# Synth_2.net
KiCad netlist of a schematic drawn in EAGLE
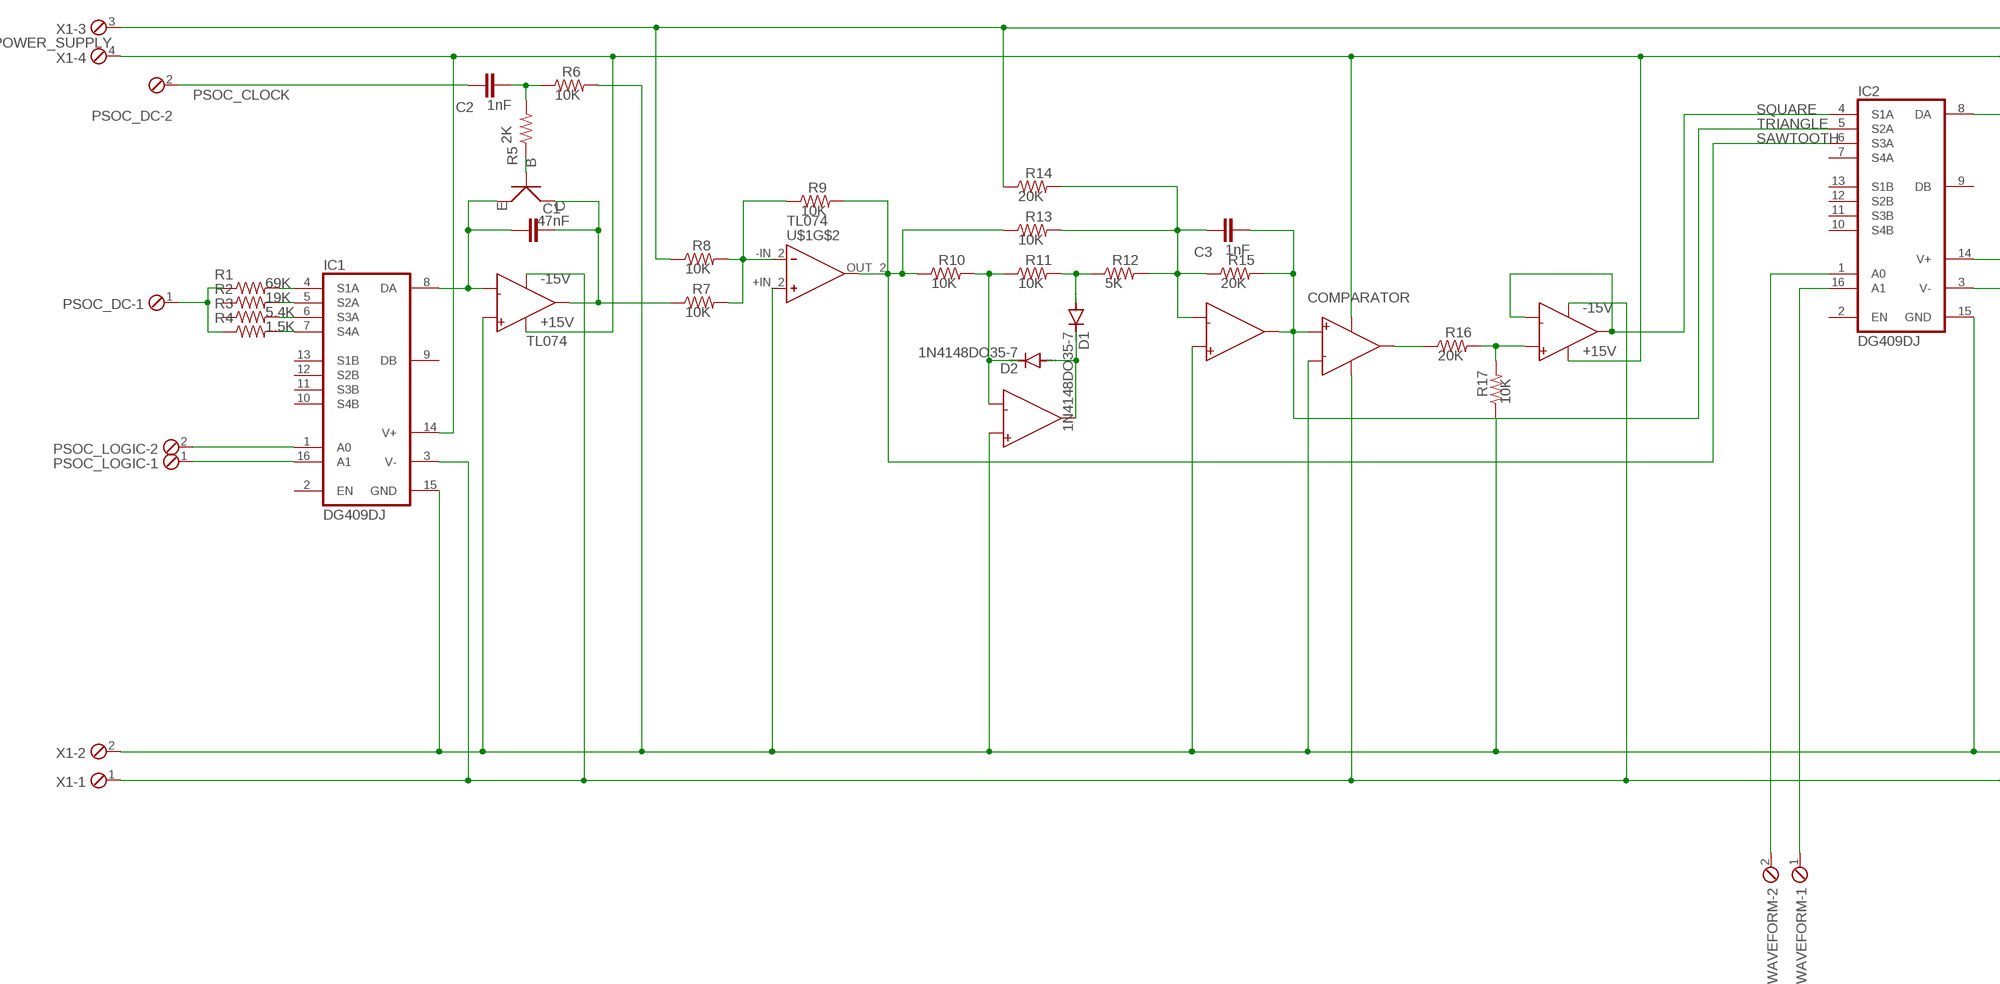
[diagram p0: schematic, sheet 1, part 1 of 2]
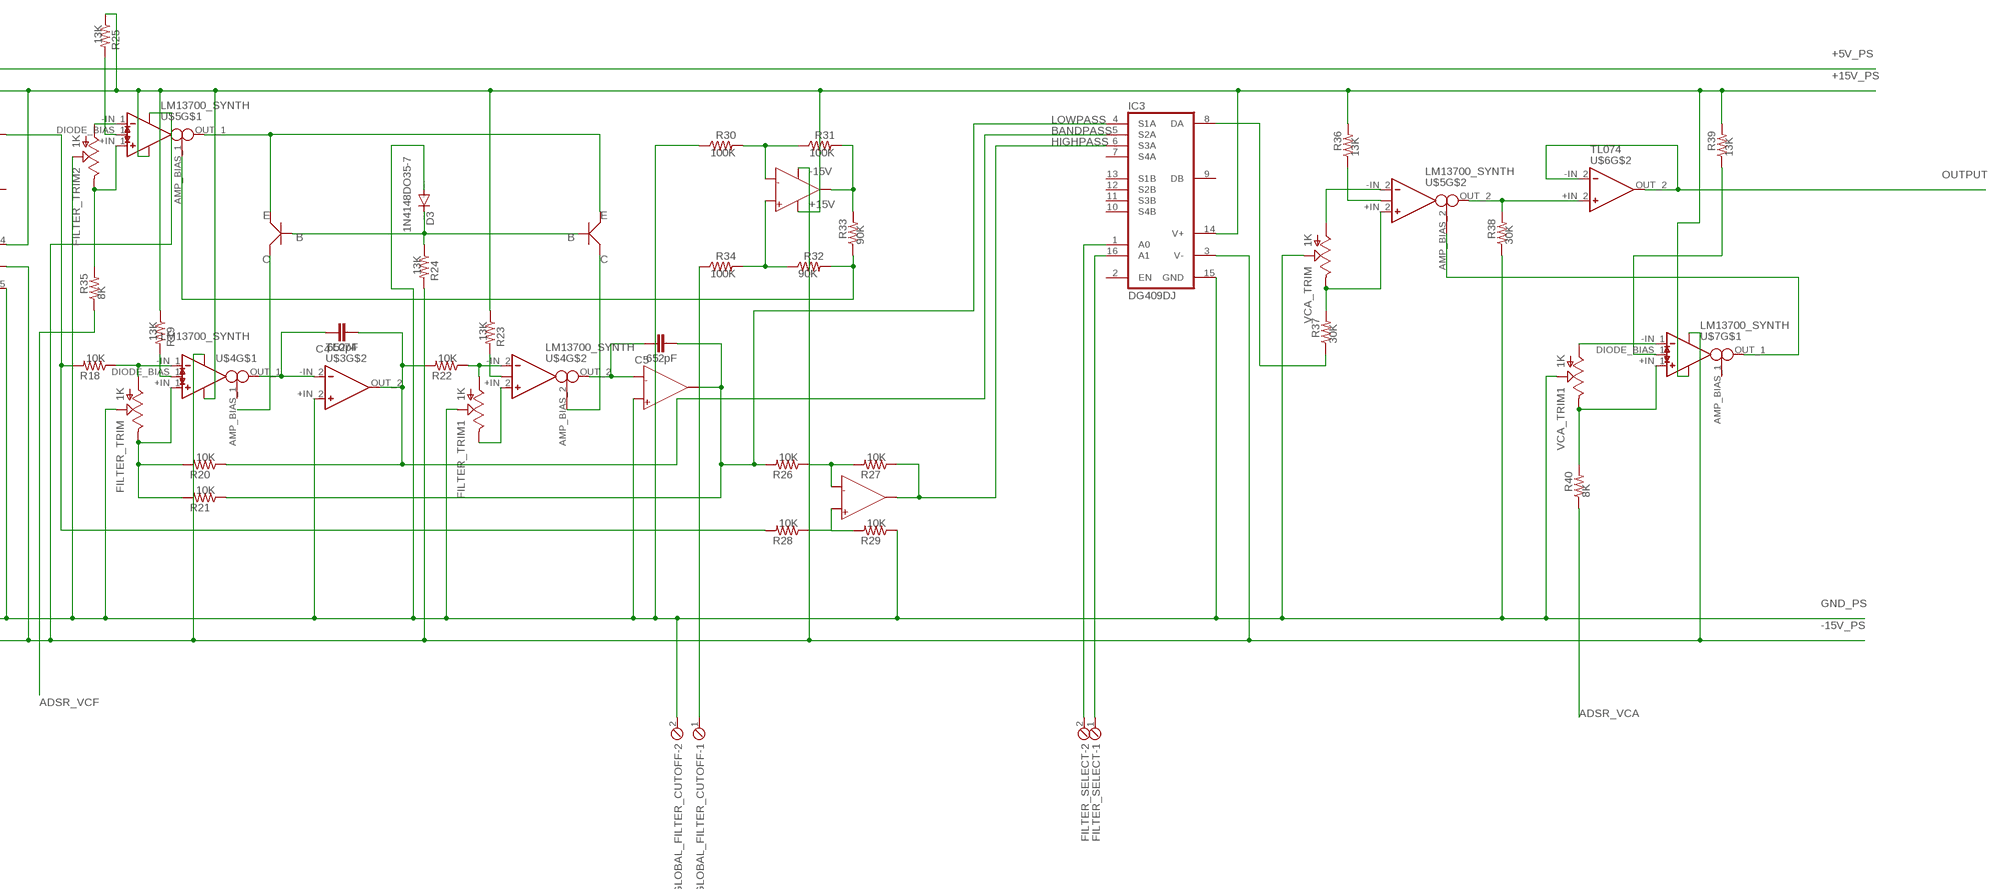
[diagram p1: schematic, sheet 1, part 2 of 2]

(export (version "E")
  (design (tool "Eeschema 10.0.6"))
  (components
    (comp (ref "C1")
      (value "C-EU025-024X044")
      (footprint "eagle-import:C025-024X044")
      (fields (field (name "SPICEPREFIX") "C") (field (name "SPICEPREFIX_1") "47nF"))
      (libsource (lib "eagle-import") (part "C-EU025-024X044"))
    )
    (comp (ref "C2")
      (value "C-EU025-024X044")
      (footprint "eagle-import:C025-024X044")
      (fields (field (name "SPICEPREFIX") "C") (field (name "SPICEPREFIX_1") "1nF"))
      (libsource (lib "eagle-import") (part "C-EU025-024X044"))
    )
    (comp (ref "C3")
      (value "C-EU025-024X044")
      (footprint "eagle-import:C025-024X044")
      (fields (field (name "SPICEPREFIX") "C") (field (name "SPICEPREFIX_1") "1nF"))
      (libsource (lib "eagle-import") (part "C-EU025-024X044"))
    )
    (comp (ref "C4")
      (value "C-EU025-024X044")
      (footprint "eagle-import:C025-024X044")
      (fields (field (name "SPICEPREFIX") "C") (field (name "SPICEPREFIX_1") "652pF"))
      (libsource (lib "eagle-import") (part "C-EU025-024X044"))
    )
    (comp (ref "C5")
      (value "C-EU025-024X044")
      (footprint "eagle-import:C025-024X044")
      (fields (field (name "SPICEPREFIX") "C") (field (name "SPICEPREFIX_1") "652pF"))
      (libsource (lib "eagle-import") (part "C-EU025-024X044"))
    )
    (comp (ref "D1")
      (value "1N4148DO35-7")
      (footprint "eagle-import:DO35-7")
      (libsource (lib "eagle-import") (part "1N4148DO35-7"))
    )
    (comp (ref "D2")
      (value "1N4148DO35-7")
      (footprint "eagle-import:DO35-7")
      (libsource (lib "eagle-import") (part "1N4148DO35-7"))
    )
    (comp (ref "D3")
      (value "1N4148DO35-7")
      (footprint "eagle-import:DO35-7")
      (libsource (lib "eagle-import") (part "1N4148DO35-7"))
    )
    (comp (ref "FILTER_SELECT")
      (value "MPT2")
      (footprint "eagle-import:2POL254")
      (libsource (lib "eagle-import") (part "MPT2"))
    )
    (comp (ref "FILTER_TRIM")
      (value "TRIM_US-CT6")
      (footprint "eagle-import:CT6")
      (fields (field (name "POPULARITY") "2") (field (name "POPULARITY_1") "1K"))
      (libsource (lib "eagle-import") (part "TRIM_US-CT6"))
    )
    (comp (ref "FILTER_TRIM1")
      (value "TRIM_US-CT6")
      (footprint "eagle-import:CT6")
      (fields (field (name "POPULARITY") "2") (field (name "POPULARITY_1") "1K"))
      (libsource (lib "eagle-import") (part "TRIM_US-CT6"))
    )
    (comp (ref "FILTER_TRIM2")
      (value "TRIM_US-CT6")
      (footprint "eagle-import:CT6")
      (fields (field (name "POPULARITY") "2") (field (name "POPULARITY_1") "1K"))
      (libsource (lib "eagle-import") (part "TRIM_US-CT6"))
    )
    (comp (ref "GLOBAL_FILTER_CUTOFF")
      (value "MPT2")
      (footprint "eagle-import:2POL254")
      (libsource (lib "eagle-import") (part "MPT2"))
    )
    (comp (ref "IC1")
      (value "DG409DJ")
      (footprint "eagle-import:DIL16")
      (fields (field (name "MF") "INTERSIL"))
      (libsource (lib "eagle-import") (part "DG409DJ"))
    )
    (comp (ref "IC2")
      (value "DG409DJ")
      (footprint "eagle-import:DIL16")
      (fields (field (name "MF") "INTERSIL"))
      (libsource (lib "eagle-import") (part "DG409DJ"))
    )
    (comp (ref "IC3")
      (value "DG409DJ")
      (footprint "eagle-import:DIL16")
      (fields (field (name "MF") "INTERSIL"))
      (libsource (lib "eagle-import") (part "DG409DJ"))
    )
    (comp (ref "LM293")
      (value "LM293")
      (footprint "eagle-import:LM293")
      (libsource (lib "eagle-import") (part "LM293"))
    )
    (comp (ref "PSOC_DC")
      (value "MPT2")
      (footprint "eagle-import:2POL254")
      (libsource (lib "eagle-import") (part "MPT2"))
    )
    (comp (ref "PSOC_LOGIC")
      (value "MPT2")
      (footprint "eagle-import:2POL254")
      (libsource (lib "eagle-import") (part "MPT2"))
    )
    (comp (ref "R1")
      (value "R-US_0204/7")
      (footprint "eagle-import:0204_7")
      (fields (field (name "SPICEPREFIX") "R") (field (name "SPICEPREFIX_1") "69K"))
      (libsource (lib "eagle-import") (part "R-US_0204/7"))
    )
    (comp (ref "R2")
      (value "R-US_0204/7")
      (footprint "eagle-import:0204_7")
      (fields (field (name "SPICEPREFIX") "R") (field (name "SPICEPREFIX_1") "19K"))
      (libsource (lib "eagle-import") (part "R-US_0204/7"))
    )
    (comp (ref "R3")
      (value "R-US_0204/7")
      (footprint "eagle-import:0204_7")
      (fields (field (name "SPICEPREFIX") "R") (field (name "SPICEPREFIX_1") "5.4K"))
      (libsource (lib "eagle-import") (part "R-US_0204/7"))
    )
    (comp (ref "R4")
      (value "R-US_0204/7")
      (footprint "eagle-import:0204_7")
      (fields (field (name "SPICEPREFIX") "R") (field (name "SPICEPREFIX_1") "1.5K"))
      (libsource (lib "eagle-import") (part "R-US_0204/7"))
    )
    (comp (ref "R5")
      (value "R-US_0204/7")
      (footprint "eagle-import:0204_7")
      (fields (field (name "SPICEPREFIX") "R") (field (name "SPICEPREFIX_1") "2K"))
      (libsource (lib "eagle-import") (part "R-US_0204/7"))
    )
    (comp (ref "R6")
      (value "R-US_0204/7")
      (footprint "eagle-import:0204_7")
      (fields (field (name "SPICEPREFIX") "R") (field (name "SPICEPREFIX_1") "10K"))
      (libsource (lib "eagle-import") (part "R-US_0204/7"))
    )
    (comp (ref "R7")
      (value "R-US_0204/7")
      (footprint "eagle-import:0204_7")
      (fields (field (name "SPICEPREFIX") "R") (field (name "SPICEPREFIX_1") "10K"))
      (libsource (lib "eagle-import") (part "R-US_0204/7"))
    )
    (comp (ref "R8")
      (value "R-US_0204/7")
      (footprint "eagle-import:0204_7")
      (fields (field (name "SPICEPREFIX") "R") (field (name "SPICEPREFIX_1") "10K"))
      (libsource (lib "eagle-import") (part "R-US_0204/7"))
    )
    (comp (ref "R9")
      (value "R-US_0204/7")
      (footprint "eagle-import:0204_7")
      (fields (field (name "SPICEPREFIX") "R") (field (name "SPICEPREFIX_1") "10K"))
      (libsource (lib "eagle-import") (part "R-US_0204/7"))
    )
    (comp (ref "R10")
      (value "R-US_0204/7")
      (footprint "eagle-import:0204_7")
      (fields (field (name "SPICEPREFIX") "R") (field (name "SPICEPREFIX_1") "10K"))
      (libsource (lib "eagle-import") (part "R-US_0204/7"))
    )
    (comp (ref "R11")
      (value "R-US_0204/7")
      (footprint "eagle-import:0204_7")
      (fields (field (name "SPICEPREFIX") "R") (field (name "SPICEPREFIX_1") "10K"))
      (libsource (lib "eagle-import") (part "R-US_0204/7"))
    )
    (comp (ref "R12")
      (value "R-US_0204/7")
      (footprint "eagle-import:0204_7")
      (fields (field (name "SPICEPREFIX") "R") (field (name "SPICEPREFIX_1") "5K"))
      (libsource (lib "eagle-import") (part "R-US_0204/7"))
    )
    (comp (ref "R13")
      (value "R-US_0204/7")
      (footprint "eagle-import:0204_7")
      (fields (field (name "SPICEPREFIX") "R") (field (name "SPICEPREFIX_1") "10K"))
      (libsource (lib "eagle-import") (part "R-US_0204/7"))
    )
    (comp (ref "R14")
      (value "R-US_0204/7")
      (footprint "eagle-import:0204_7")
      (fields (field (name "SPICEPREFIX") "R") (field (name "SPICEPREFIX_1") "20K"))
      (libsource (lib "eagle-import") (part "R-US_0204/7"))
    )
    (comp (ref "R15")
      (value "R-US_0204/7")
      (footprint "eagle-import:0204_7")
      (fields (field (name "SPICEPREFIX") "R") (field (name "SPICEPREFIX_1") "20K"))
      (libsource (lib "eagle-import") (part "R-US_0204/7"))
    )
    (comp (ref "R16")
      (value "R-US_0204/7")
      (footprint "eagle-import:0204_7")
      (fields (field (name "SPICEPREFIX") "R") (field (name "SPICEPREFIX_1") "20K"))
      (libsource (lib "eagle-import") (part "R-US_0204/7"))
    )
    (comp (ref "R17")
      (value "R-US_0204/7")
      (footprint "eagle-import:0204_7")
      (fields (field (name "SPICEPREFIX") "R") (field (name "SPICEPREFIX_1") "10K"))
      (libsource (lib "eagle-import") (part "R-US_0204/7"))
    )
    (comp (ref "R18")
      (value "R-US_0204/7")
      (footprint "eagle-import:0204_7")
      (fields (field (name "SPICEPREFIX") "R") (field (name "SPICEPREFIX_1") "10K"))
      (libsource (lib "eagle-import") (part "R-US_0204/7"))
    )
    (comp (ref "R19")
      (value "R-US_0204/7")
      (footprint "eagle-import:0204_7")
      (fields (field (name "SPICEPREFIX") "R") (field (name "SPICEPREFIX_1") "13K"))
      (libsource (lib "eagle-import") (part "R-US_0204/7"))
    )
    (comp (ref "R20")
      (value "R-US_0204/7")
      (footprint "eagle-import:0204_7")
      (fields (field (name "SPICEPREFIX") "R") (field (name "SPICEPREFIX_1") "10K"))
      (libsource (lib "eagle-import") (part "R-US_0204/7"))
    )
    (comp (ref "R21")
      (value "R-US_0204/7")
      (footprint "eagle-import:0204_7")
      (fields (field (name "SPICEPREFIX") "R") (field (name "SPICEPREFIX_1") "10K"))
      (libsource (lib "eagle-import") (part "R-US_0204/7"))
    )
    (comp (ref "R22")
      (value "R-US_0204/7")
      (footprint "eagle-import:0204_7")
      (fields (field (name "SPICEPREFIX") "R") (field (name "SPICEPREFIX_1") "10K"))
      (libsource (lib "eagle-import") (part "R-US_0204/7"))
    )
    (comp (ref "R23")
      (value "R-US_0204/7")
      (footprint "eagle-import:0204_7")
      (fields (field (name "SPICEPREFIX") "R") (field (name "SPICEPREFIX_1") "13K"))
      (libsource (lib "eagle-import") (part "R-US_0204/7"))
    )
    (comp (ref "R24")
      (value "R-US_0204/7")
      (footprint "eagle-import:0204_7")
      (fields (field (name "SPICEPREFIX") "R") (field (name "SPICEPREFIX_1") "13K"))
      (libsource (lib "eagle-import") (part "R-US_0204/7"))
    )
    (comp (ref "R25")
      (value "R-US_0204/7")
      (footprint "eagle-import:0204_7")
      (fields (field (name "SPICEPREFIX") "R") (field (name "SPICEPREFIX_1") "13K"))
      (libsource (lib "eagle-import") (part "R-US_0204/7"))
    )
    (comp (ref "R26")
      (value "R-US_0204/7")
      (footprint "eagle-import:0204_7")
      (fields (field (name "SPICEPREFIX") "R") (field (name "SPICEPREFIX_1") "10K"))
      (libsource (lib "eagle-import") (part "R-US_0204/7"))
    )
    (comp (ref "R27")
      (value "R-US_0204/7")
      (footprint "eagle-import:0204_7")
      (fields (field (name "SPICEPREFIX") "R") (field (name "SPICEPREFIX_1") "10K"))
      (libsource (lib "eagle-import") (part "R-US_0204/7"))
    )
    (comp (ref "R28")
      (value "R-US_0204/7")
      (footprint "eagle-import:0204_7")
      (fields (field (name "SPICEPREFIX") "R") (field (name "SPICEPREFIX_1") "10K"))
      (libsource (lib "eagle-import") (part "R-US_0204/7"))
    )
    (comp (ref "R29")
      (value "R-US_0204/7")
      (footprint "eagle-import:0204_7")
      (fields (field (name "SPICEPREFIX") "R") (field (name "SPICEPREFIX_1") "10K"))
      (libsource (lib "eagle-import") (part "R-US_0204/7"))
    )
    (comp (ref "R30")
      (value "R-US_0204/7")
      (footprint "eagle-import:0204_7")
      (fields (field (name "SPICEPREFIX") "R") (field (name "SPICEPREFIX_1") "100K"))
      (libsource (lib "eagle-import") (part "R-US_0204/7"))
    )
    (comp (ref "R31")
      (value "R-US_0204/7")
      (footprint "eagle-import:0204_7")
      (fields (field (name "SPICEPREFIX") "R") (field (name "SPICEPREFIX_1") "100K"))
      (libsource (lib "eagle-import") (part "R-US_0204/7"))
    )
    (comp (ref "R32")
      (value "R-US_0204/7")
      (footprint "eagle-import:0204_7")
      (fields (field (name "SPICEPREFIX") "R") (field (name "SPICEPREFIX_1") "90K"))
      (libsource (lib "eagle-import") (part "R-US_0204/7"))
    )
    (comp (ref "R33")
      (value "R-US_0204/7")
      (footprint "eagle-import:0204_7")
      (fields (field (name "SPICEPREFIX") "R") (field (name "SPICEPREFIX_1") "90K"))
      (libsource (lib "eagle-import") (part "R-US_0204/7"))
    )
    (comp (ref "R34")
      (value "R-US_0204/7")
      (footprint "eagle-import:0204_7")
      (fields (field (name "SPICEPREFIX") "R") (field (name "SPICEPREFIX_1") "100K"))
      (libsource (lib "eagle-import") (part "R-US_0204/7"))
    )
    (comp (ref "R35")
      (value "R-US_0204/7")
      (footprint "eagle-import:0204_7")
      (fields (field (name "SPICEPREFIX") "R") (field (name "SPICEPREFIX_1") "8K"))
      (libsource (lib "eagle-import") (part "R-US_0204/7"))
    )
    (comp (ref "R36")
      (value "R-US_0204/7")
      (footprint "eagle-import:0204_7")
      (fields (field (name "SPICEPREFIX") "R") (field (name "SPICEPREFIX_1") "13K"))
      (libsource (lib "eagle-import") (part "R-US_0204/7"))
    )
    (comp (ref "R37")
      (value "R-US_0204/7")
      (footprint "eagle-import:0204_7")
      (fields (field (name "SPICEPREFIX") "R") (field (name "SPICEPREFIX_1") "30K"))
      (libsource (lib "eagle-import") (part "R-US_0204/7"))
    )
    (comp (ref "R38")
      (value "R-US_0204/7")
      (footprint "eagle-import:0204_7")
      (fields (field (name "SPICEPREFIX") "R") (field (name "SPICEPREFIX_1") "30K"))
      (libsource (lib "eagle-import") (part "R-US_0204/7"))
    )
    (comp (ref "R39")
      (value "R-US_0204/7")
      (footprint "eagle-import:0204_7")
      (fields (field (name "SPICEPREFIX") "R") (field (name "SPICEPREFIX_1") "13K"))
      (libsource (lib "eagle-import") (part "R-US_0204/7"))
    )
    (comp (ref "R40")
      (value "R-US_0204/7")
      (footprint "eagle-import:0204_7")
      (fields (field (name "SPICEPREFIX") "R") (field (name "SPICEPREFIX_1") "8K"))
      (libsource (lib "eagle-import") (part "R-US_0204/7"))
    )
    (comp (ref "U$1")
      (value "TL074")
      (footprint "eagle-import:TL074")
      (libsource (lib "eagle-import") (part "TL074"))
    )
    (comp (ref "U$2")
      (value "MPQ2907A")
      (footprint "eagle-import:MPQ2907A")
      (libsource (lib "eagle-import") (part "MPQ2907A"))
    )
    (comp (ref "U$3")
      (value "TL074")
      (footprint "eagle-import:TL074")
      (libsource (lib "eagle-import") (part "TL074"))
    )
    (comp (ref "U$4")
      (value "LM13700_SYNTH")
      (footprint "eagle-import:LM13700_SYNTH")
      (libsource (lib "eagle-import") (part "LM13700_SYNTH"))
    )
    (comp (ref "U$5")
      (value "LM13700_SYNTH")
      (footprint "eagle-import:LM13700_SYNTH")
      (libsource (lib "eagle-import") (part "LM13700_SYNTH"))
    )
    (comp (ref "U$6")
      (value "TL074")
      (footprint "eagle-import:TL074")
      (libsource (lib "eagle-import") (part "TL074"))
    )
    (comp (ref "U$7")
      (value "LM13700_SYNTH")
      (footprint "eagle-import:LM13700_SYNTH")
      (libsource (lib "eagle-import") (part "LM13700_SYNTH"))
    )
    (comp (ref "VCA_TRIM")
      (value "TRIM_US-CT6")
      (footprint "eagle-import:CT6")
      (fields (field (name "POPULARITY") "2") (field (name "POPULARITY_1") "1K"))
      (libsource (lib "eagle-import") (part "TRIM_US-CT6"))
    )
    (comp (ref "VCA_TRIM1")
      (value "TRIM_US-CT6")
      (footprint "eagle-import:CT6")
      (fields (field (name "POPULARITY") "2") (field (name "POPULARITY_1") "1K"))
      (libsource (lib "eagle-import") (part "TRIM_US-CT6"))
    )
    (comp (ref "WAVEFORM")
      (value "MPT2")
      (footprint "eagle-import:2POL254")
      (libsource (lib "eagle-import") (part "MPT2"))
    )
    (comp (ref "X1")
      (value "POWER_SUPPLY")
      (footprint "eagle-import:4POL254")
      (libsource (lib "eagle-import") (part "MPT4"))
    )
  )
  (nets
    (net (code "1") (name "/+5V_PS") (class "Default")
      (node (ref "R14") (pin "1") (pinfunction "1_1") (pintype "passive"))
      (node (ref "R8") (pin "1") (pinfunction "1_1") (pintype "passive"))
      (node (ref "X1") (pin "3") (pinfunction "1_3") (pintype "passive"))
    )
    (net (code "2") (name "/+15V_PS") (class "Default")
      (node (ref "IC1") (pin "14") (pinfunction "V+_14") (pintype "power_in"))
      (node (ref "IC2") (pin "14") (pinfunction "V+_14") (pintype "power_in"))
      (node (ref "IC3") (pin "14") (pinfunction "V+_14") (pintype "power_in"))
      (node (ref "LM293") (pin "VCC") (pinfunction "VCC_VCC") (pintype "power_in"))
      (node (ref "R19") (pin "1") (pinfunction "1_1") (pintype "passive"))
      (node (ref "R23") (pin "1") (pinfunction "1_1") (pintype "passive"))
      (node (ref "R25") (pin "1") (pinfunction "1_1") (pintype "passive"))
      (node (ref "R36") (pin "2") (pinfunction "2_2") (pintype "passive"))
      (node (ref "R39") (pin "2") (pinfunction "2_2") (pintype "passive"))
      (node (ref "U$1") (pin "VCC+") (pinfunction "VCC+_VCC+") (pintype "power_in"))
      (node (ref "U$3") (pin "VCC+") (pinfunction "VCC+_VCC+") (pintype "power_in"))
      (node (ref "U$4") (pin "+V") (pinfunction "+V_+V") (pintype "power_in"))
      (node (ref "U$5") (pin "+V") (pinfunction "+V_+V") (pintype "power_in"))
      (node (ref "U$6") (pin "VCC+") (pinfunction "VCC+_VCC+") (pintype "power_in"))
      (node (ref "U$7") (pin "+V") (pinfunction "+V_+V") (pintype "power_in"))
      (node (ref "X1") (pin "4") (pinfunction "1_4") (pintype "passive"))
    )
    (net (code "3") (name "/-15V_PS") (class "Default")
      (node (ref "IC1") (pin "3") (pinfunction "V-_3") (pintype "power_in"))
      (node (ref "IC2") (pin "3") (pinfunction "V-_3") (pintype "power_in"))
      (node (ref "IC3") (pin "3") (pinfunction "V-_3") (pintype "power_in"))
      (node (ref "LM293") (pin "GND") (pinfunction "GND_GND") (pintype "input"))
      (node (ref "R24") (pin "2") (pinfunction "2_2") (pintype "passive"))
      (node (ref "U$1") (pin "VCC-") (pinfunction "VCC-_VCC-") (pintype "power_in"))
      (node (ref "U$3") (pin "VCC-") (pinfunction "VCC-_VCC-") (pintype "power_in"))
      (node (ref "U$4") (pin "-V") (pinfunction "-V_-V") (pintype "power_in"))
      (node (ref "U$5") (pin "-V") (pinfunction "-V_-V") (pintype "power_in"))
      (node (ref "U$6") (pin "VCC-") (pinfunction "VCC-_VCC-") (pintype "power_in"))
      (node (ref "U$7") (pin "-V") (pinfunction "-V_-V") (pintype "power_in"))
      (node (ref "X1") (pin "1") (pinfunction "1_1") (pintype "passive"))
    )
    (net (code "4") (name "/ADSR_VCA") (class "Default")
      (node (ref "R40") (pin "2") (pinfunction "2_2") (pintype "passive"))
      (node (ref "U$7") (pin "+IN_1") (pinfunction "+IN_1_+IN_1") (pintype "input"))
      (node (ref "VCA_TRIM1") (pin "E") (pinfunction "E_E") (pintype "passive"))
    )
    (net (code "5") (name "/ADSR_VCF") (class "Default")
      (node (ref "R35") (pin "1") (pinfunction "1_1") (pintype "passive"))
    )
    (net (code "6") (name "/BANDPASS") (class "Default")
      (node (ref "C4") (pin "2") (pinfunction "2_2") (pintype "passive"))
      (node (ref "IC3") (pin "5") (pinfunction "S2A_5") (pintype "passive"))
      (node (ref "R20") (pin "1") (pinfunction "1_1") (pintype "passive"))
      (node (ref "R22") (pin "2") (pinfunction "2_2") (pintype "passive"))
      (node (ref "U$3") (pin "OUT_2") (pinfunction "OUT_2_OUT_2") (pintype "output"))
    )
    (net (code "7") (name "/COMPARATOR") (class "Default")
      (node (ref "LM293") (pin "OUT_1") (pinfunction "OUT_1_OUT_1") (pintype "output"))
      (node (ref "R16") (pin "1") (pinfunction "1_1") (pintype "passive"))
    )
    (net (code "8") (name "/GND_PS") (class "Default")
      (node (ref "D3") (pin "A") (pinfunction "A_A") (pintype "passive"))
      (node (ref "FILTER_TRIM") (pin "S") (pinfunction "S_S") (pintype "passive"))
      (node (ref "FILTER_TRIM1") (pin "S") (pinfunction "S_S") (pintype "passive"))
      (node (ref "FILTER_TRIM2") (pin "S") (pinfunction "S_S") (pintype "passive"))
      (node (ref "GLOBAL_FILTER_CUTOFF") (pin "2") (pinfunction "1_2") (pintype "passive"))
      (node (ref "IC1") (pin "15") (pinfunction "GND_15") (pintype "power_in"))
      (node (ref "IC2") (pin "15") (pinfunction "GND_15") (pintype "power_in"))
      (node (ref "IC3") (pin "15") (pinfunction "GND_15") (pintype "power_in"))
      (node (ref "LM293") (pin "-IN_1") (pinfunction "-IN_1_-IN_1") (pintype "input"))
      (node (ref "R17") (pin "1") (pinfunction "1_1") (pintype "passive"))
      (node (ref "R29") (pin "1") (pinfunction "1_1") (pintype "passive"))
      (node (ref "R30") (pin "1") (pinfunction "1_1") (pintype "passive"))
      (node (ref "R38") (pin "1") (pinfunction "1_1") (pintype "passive"))
      (node (ref "R6") (pin "2") (pinfunction "2_2") (pintype "passive"))
      (node (ref "U$1") (pin "+IN_1") (pinfunction "+IN_1_+IN_1") (pintype "input"))
      (node (ref "U$1") (pin "+IN_2") (pinfunction "+IN_2_+IN_2") (pintype "input"))
      (node (ref "U$1") (pin "+IN_3") (pinfunction "+IN_3_+IN_3") (pintype "input"))
      (node (ref "U$1") (pin "+IN_4") (pinfunction "+IN_4_+IN_4") (pintype "input"))
      (node (ref "U$3") (pin "+IN_2") (pinfunction "+IN_2_+IN_2") (pintype "input"))
      (node (ref "U$3") (pin "+IN_4") (pinfunction "+IN_4_+IN_4") (pintype "input"))
      (node (ref "VCA_TRIM") (pin "S") (pinfunction "S_S") (pintype "passive"))
      (node (ref "VCA_TRIM1") (pin "S") (pinfunction "S_S") (pintype "passive"))
      (node (ref "X1") (pin "2") (pinfunction "1_2") (pintype "passive"))
    )
    (net (code "9") (name "/HIGHPASS") (class "Default")
      (node (ref "IC3") (pin "6") (pinfunction "S3A_6") (pintype "passive"))
      (node (ref "R27") (pin "1") (pinfunction "1_1") (pintype "passive"))
      (node (ref "U$3") (pin "OUT_3") (pinfunction "OUT_3_OUT_3") (pintype "output"))
    )
    (net (code "10") (name "/LOWPASS") (class "Default")
      (node (ref "C5") (pin "2") (pinfunction "2_2") (pintype "passive"))
      (node (ref "IC3") (pin "4") (pinfunction "S1A_4") (pintype "passive"))
      (node (ref "R21") (pin "1") (pinfunction "1_1") (pintype "passive"))
      (node (ref "R26") (pin "2") (pinfunction "2_2") (pintype "passive"))
      (node (ref "U$3") (pin "OUT_4") (pinfunction "OUT_4_OUT_4") (pintype "input"))
    )
    (net (code "11") (name "/OUTPUT") (class "Default")
      (node (ref "U$6") (pin "-IN_2") (pinfunction "-IN_2_-IN_2") (pintype "input"))
      (node (ref "U$6") (pin "OUT_2") (pinfunction "OUT_2_OUT_2") (pintype "output"))
    )
    (net (code "12") (name "/PSOC_CLOCK") (class "Default")
      (node (ref "C2") (pin "1") (pinfunction "1_1") (pintype "passive"))
      (node (ref "PSOC_DC") (pin "2") (pinfunction "1_2") (pintype "passive"))
    )
    (net (code "13") (name "/SAWTOOTH") (class "Default")
      (node (ref "IC2") (pin "6") (pinfunction "S3A_6") (pintype "passive"))
      (node (ref "R10") (pin "1") (pinfunction "1_1") (pintype "passive"))
      (node (ref "R13") (pin "1") (pinfunction "1_1") (pintype "passive"))
      (node (ref "R9") (pin "2") (pinfunction "2_2") (pintype "passive"))
      (node (ref "U$1") (pin "OUT_2") (pinfunction "OUT_2_OUT_2") (pintype "output"))
    )
    (net (code "14") (name "/SQUARE") (class "Default")
      (node (ref "IC2") (pin "4") (pinfunction "S1A_4") (pintype "passive"))
      (node (ref "U$3") (pin "-IN_1") (pinfunction "-IN_1_-IN_1") (pintype "input"))
      (node (ref "U$3") (pin "OUT_1") (pinfunction "OUT_1_OUT_1") (pintype "output"))
    )
    (net (code "15") (name "/TL074") (class "Default")
      (node (ref "C1") (pin "1") (pinfunction "1_1") (pintype "passive"))
      (node (ref "IC1") (pin "8") (pinfunction "DA_8") (pintype "passive"))
      (node (ref "U$1") (pin "-IN_1") (pinfunction "-IN_1_-IN_1") (pintype "input"))
      (node (ref "U$2") (pin "Q1_E") (pinfunction "E_Q1_E") (pintype "bidirectional"))
    )
    (net (code "16") (name "/TRIANGLE") (class "Default")
      (node (ref "C3") (pin "2") (pinfunction "2_2") (pintype "passive"))
      (node (ref "IC2") (pin "5") (pinfunction "S2A_5") (pintype "passive"))
      (node (ref "LM293") (pin "+IN_1") (pinfunction "+IN_1_+IN_1") (pintype "input"))
      (node (ref "R15") (pin "2") (pinfunction "2_2") (pintype "passive"))
      (node (ref "U$1") (pin "OUT_4") (pinfunction "OUT_4_OUT_4") (pintype "input"))
    )
    (net (code "17") (name "Net-(C2-Pad2)") (class "Default")
      (node (ref "C2") (pin "2") (pinfunction "2_2") (pintype "passive"))
      (node (ref "R5") (pin "2") (pinfunction "2_2") (pintype "passive"))
      (node (ref "R6") (pin "1") (pinfunction "1_1") (pintype "passive"))
    )
    (net (code "18") (name "Net-(C3-Pad1)") (class "Default")
      (node (ref "C3") (pin "1") (pinfunction "1_1") (pintype "passive"))
      (node (ref "R12") (pin "2") (pinfunction "2_2") (pintype "passive"))
      (node (ref "R13") (pin "2") (pinfunction "2_2") (pintype "passive"))
      (node (ref "R14") (pin "2") (pinfunction "2_2") (pintype "passive"))
      (node (ref "R15") (pin "1") (pinfunction "1_1") (pintype "passive"))
      (node (ref "U$1") (pin "-IN_4") (pinfunction "-IN_4_-IN_4") (pintype "input"))
    )
    (net (code "19") (name "Net-(C4-Pad1)") (class "Default")
      (node (ref "C4") (pin "1") (pinfunction "1_1") (pintype "passive"))
      (node (ref "U$3") (pin "-IN_2") (pinfunction "-IN_2_-IN_2") (pintype "input"))
      (node (ref "U$4") (pin "OUT_1") (pinfunction "OUT_1_OUT_1") (pintype "output"))
    )
    (net (code "20") (name "Net-(C5-Pad1)") (class "Default")
      (node (ref "C5") (pin "1") (pinfunction "1_1") (pintype "passive"))
      (node (ref "U$3") (pin "-IN_4") (pinfunction "-IN_4_-IN_4") (pintype "input"))
      (node (ref "U$4") (pin "OUT_2") (pinfunction "OUT_2_OUT_2") (pintype "output"))
    )
    (net (code "21") (name "Net-(D1-PadA)") (class "Default")
      (node (ref "D1") (pin "A") (pinfunction "A_A") (pintype "passive"))
      (node (ref "R11") (pin "2") (pinfunction "2_2") (pintype "passive"))
      (node (ref "R12") (pin "1") (pinfunction "1_1") (pintype "passive"))
    )
    (net (code "22") (name "Net-(D1-PadC)") (class "Default")
      (node (ref "D1") (pin "C") (pinfunction "C_C") (pintype "passive"))
      (node (ref "D2") (pin "A") (pinfunction "A_A") (pintype "passive"))
      (node (ref "U$1") (pin "OUT_3") (pinfunction "OUT_3_OUT_3") (pintype "output"))
    )
    (net (code "23") (name "Net-(D2-PadC)") (class "Default")
      (node (ref "D2") (pin "C") (pinfunction "C_C") (pintype "passive"))
      (node (ref "R10") (pin "2") (pinfunction "2_2") (pintype "passive"))
      (node (ref "R11") (pin "1") (pinfunction "1_1") (pintype "passive"))
      (node (ref "U$1") (pin "-IN_3") (pinfunction "-IN_3_-IN_3") (pintype "input"))
    )
    (net (code "24") (name "Net-(FILTER_SELECTB-1)") (class "Default")
      (node (ref "FILTER_SELECT") (pin "2") (pinfunction "1_2") (pintype "passive"))
      (node (ref "IC3") (pin "1") (pinfunction "A0_1") (pintype "input"))
    )
    (net (code "25") (name "Net-(FILTER_TRIM-PadA)") (class "Default")
      (node (ref "FILTER_TRIM") (pin "A") (pinfunction "A_A") (pintype "passive"))
      (node (ref "R18") (pin "1") (pinfunction "1_1") (pintype "passive"))
      (node (ref "U$4") (pin "-IN_1") (pinfunction "-IN_1_-IN_1") (pintype "input"))
    )
    (net (code "26") (name "Net-(FILTER_TRIM-PadE)") (class "Default")
      (node (ref "FILTER_TRIM") (pin "E") (pinfunction "E_E") (pintype "passive"))
      (node (ref "R20") (pin "2") (pinfunction "2_2") (pintype "passive"))
      (node (ref "R21") (pin "2") (pinfunction "2_2") (pintype "passive"))
      (node (ref "U$4") (pin "+IN_1") (pinfunction "+IN_1_+IN_1") (pintype "input"))
    )
    (net (code "27") (name "Net-(FILTER_TRIM1-PadA)") (class "Default")
      (node (ref "FILTER_TRIM1") (pin "A") (pinfunction "A_A") (pintype "passive"))
      (node (ref "R22") (pin "1") (pinfunction "1_1") (pintype "passive"))
      (node (ref "U$4") (pin "-IN_2") (pinfunction "-IN_2_-IN_2") (pintype "input"))
    )
    (net (code "28") (name "Net-(FILTER_TRIM1-PadE)") (class "Default")
      (node (ref "FILTER_TRIM1") (pin "E") (pinfunction "E_E") (pintype "passive"))
      (node (ref "U$4") (pin "+IN_2") (pinfunction "+IN_2_+IN_2") (pintype "input"))
    )
    (net (code "29") (name "Net-(FILTER_TRIM2-PadA)") (class "Default")
      (node (ref "FILTER_TRIM2") (pin "A") (pinfunction "A_A") (pintype "passive"))
      (node (ref "U$5") (pin "-IN_1") (pinfunction "-IN_1_-IN_1") (pintype "input"))
    )
    (net (code "30") (name "Net-(FILTER_TRIM2-PadE)") (class "Default")
      (node (ref "FILTER_TRIM2") (pin "E") (pinfunction "E_E") (pintype "passive"))
      (node (ref "R35") (pin "2") (pinfunction "2_2") (pintype "passive"))
      (node (ref "U$5") (pin "+IN_1") (pinfunction "+IN_1_+IN_1") (pintype "input"))
    )
    (net (code "31") (name "Net-(GLOBAL_FILTER_CUTOFF-Pad1)") (class "Default")
      (node (ref "GLOBAL_FILTER_CUTOFF") (pin "1") (pinfunction "1_1") (pintype "passive"))
      (node (ref "R34") (pin "1") (pinfunction "1_1") (pintype "passive"))
    )
    (net (code "32") (name "Net-(IC1-A0)") (class "Default")
      (node (ref "IC1") (pin "1") (pinfunction "A0_1") (pintype "input"))
      (node (ref "PSOC_LOGIC") (pin "2") (pinfunction "1_2") (pintype "passive"))
    )
    (net (code "33") (name "Net-(IC1-A1)") (class "Default")
      (node (ref "IC1") (pin "16") (pinfunction "A1_16") (pintype "input"))
      (node (ref "PSOC_LOGIC") (pin "1") (pinfunction "1_1") (pintype "passive"))
    )
    (net (code "34") (name "Net-(IC1-S1A)") (class "Default")
      (node (ref "IC1") (pin "4") (pinfunction "S1A_4") (pintype "passive"))
      (node (ref "R1") (pin "2") (pinfunction "2_2") (pintype "passive"))
    )
    (net (code "35") (name "Net-(IC1-S2A)") (class "Default")
      (node (ref "IC1") (pin "5") (pinfunction "S2A_5") (pintype "passive"))
      (node (ref "R2") (pin "2") (pinfunction "2_2") (pintype "passive"))
    )
    (net (code "36") (name "Net-(IC1-S3A)") (class "Default")
      (node (ref "IC1") (pin "6") (pinfunction "S3A_6") (pintype "passive"))
      (node (ref "R3") (pin "2") (pinfunction "2_2") (pintype "passive"))
    )
    (net (code "37") (name "Net-(IC1-S4A)") (class "Default")
      (node (ref "IC1") (pin "7") (pinfunction "S4A_7") (pintype "passive"))
      (node (ref "R4") (pin "2") (pinfunction "2_2") (pintype "passive"))
    )
    (net (code "38") (name "Net-(IC2-A0)") (class "Default")
      (node (ref "IC2") (pin "1") (pinfunction "A0_1") (pintype "input"))
      (node (ref "WAVEFORM") (pin "2") (pinfunction "1_2") (pintype "passive"))
    )
    (net (code "39") (name "Net-(IC2-A1)") (class "Default")
      (node (ref "IC2") (pin "16") (pinfunction "A1_16") (pintype "input"))
      (node (ref "WAVEFORM") (pin "1") (pinfunction "1_1") (pintype "passive"))
    )
    (net (code "40") (name "Net-(IC2-DA)") (class "Default")
      (node (ref "IC2") (pin "8") (pinfunction "DA_8") (pintype "passive"))
      (node (ref "R18") (pin "2") (pinfunction "2_2") (pintype "passive"))
      (node (ref "R28") (pin "2") (pinfunction "2_2") (pintype "passive"))
    )
    (net (code "41") (name "Net-(IC3-A1)") (class "Default")
      (node (ref "FILTER_SELECT") (pin "1") (pinfunction "1_1") (pintype "passive"))
      (node (ref "IC3") (pin "16") (pinfunction "A1_16") (pintype "input"))
    )
    (net (code "42") (name "Net-(IC3-DA)") (class "Default")
      (node (ref "IC3") (pin "8") (pinfunction "DA_8") (pintype "passive"))
      (node (ref "R37") (pin "1") (pinfunction "1_1") (pintype "passive"))
    )
    (net (code "43") (name "Net-(PSOC_DC-Pad1)") (class "Default")
      (node (ref "PSOC_DC") (pin "1") (pinfunction "1_1") (pintype "passive"))
      (node (ref "R1") (pin "1") (pinfunction "1_1") (pintype "passive"))
      (node (ref "R4") (pin "1") (pinfunction "1_1") (pintype "passive"))
    )
    (net (code "44") (name "Net-(R7-Pad2)") (class "Default")
      (node (ref "R7") (pin "2") (pinfunction "2_2") (pintype "passive"))
      (node (ref "R8") (pin "2") (pinfunction "2_2") (pintype "passive"))
      (node (ref "R9") (pin "1") (pinfunction "1_1") (pintype "passive"))
      (node (ref "U$1") (pin "-IN_2") (pinfunction "-IN_2_-IN_2") (pintype "input"))
    )
    (net (code "45") (name "Net-(R16-Pad2)") (class "Default")
      (node (ref "R16") (pin "2") (pinfunction "2_2") (pintype "passive"))
      (node (ref "R17") (pin "2") (pinfunction "2_2") (pintype "passive"))
      (node (ref "U$3") (pin "+IN_1") (pinfunction "+IN_1_+IN_1") (pintype "input"))
    )
    (net (code "46") (name "Net-(R19-Pad2)") (class "Default")
      (node (ref "R19") (pin "2") (pinfunction "2_2") (pintype "passive"))
      (node (ref "U$4") (pin "DIODE_BIAS_1") (pinfunction "DIODE_BIAS_1_DIODE_BIAS_1") (pintype "input"))
    )
    (net (code "47") (name "Net-(R23-Pad2)") (class "Default")
      (node (ref "R23") (pin "2") (pinfunction "2_2") (pintype "passive"))
      (node (ref "U$4") (pin "DIODE_BIAS_2") (pinfunction "DIODE_BIAS_2_DIODE_BIAS_2") (pintype "input"))
    )
    (net (code "48") (name "Net-(R25-Pad2)") (class "Default")
      (node (ref "R25") (pin "2") (pinfunction "2_2") (pintype "passive"))
      (node (ref "U$5") (pin "DIODE_BIAS_1") (pinfunction "DIODE_BIAS_1_DIODE_BIAS_1") (pintype "input"))
    )
    (net (code "49") (name "Net-(R26-Pad1)") (class "Default")
      (node (ref "R26") (pin "1") (pinfunction "1_1") (pintype "passive"))
      (node (ref "R27") (pin "2") (pinfunction "2_2") (pintype "passive"))
      (node (ref "U$3") (pin "-IN_3") (pinfunction "-IN_3_-IN_3") (pintype "input"))
    )
    (net (code "50") (name "Net-(R28-Pad1)") (class "Default")
      (node (ref "R28") (pin "1") (pinfunction "1_1") (pintype "passive"))
      (node (ref "R29") (pin "2") (pinfunction "2_2") (pintype "passive"))
      (node (ref "U$3") (pin "+IN_3") (pinfunction "+IN_3_+IN_3") (pintype "input"))
    )
    (net (code "51") (name "Net-(R30-Pad2)") (class "Default")
      (node (ref "R30") (pin "2") (pinfunction "2_2") (pintype "passive"))
      (node (ref "R31") (pin "1") (pinfunction "1_1") (pintype "passive"))
      (node (ref "U$6") (pin "-IN_1") (pinfunction "-IN_1_-IN_1") (pintype "input"))
    )
    (net (code "52") (name "Net-(R31-Pad2)") (class "Default")
      (node (ref "R31") (pin "2") (pinfunction "2_2") (pintype "passive"))
      (node (ref "R33") (pin "2") (pinfunction "2_2") (pintype "passive"))
      (node (ref "U$6") (pin "OUT_1") (pinfunction "OUT_1_OUT_1") (pintype "output"))
    )
    (net (code "53") (name "Net-(R32-Pad1)") (class "Default")
      (node (ref "R32") (pin "1") (pinfunction "1_1") (pintype "passive"))
      (node (ref "R34") (pin "2") (pinfunction "2_2") (pintype "passive"))
      (node (ref "U$6") (pin "+IN_1") (pinfunction "+IN_1_+IN_1") (pintype "input"))
    )
    (net (code "54") (name "Net-(R32-Pad2)") (class "Default")
      (node (ref "R32") (pin "2") (pinfunction "2_2") (pintype "passive"))
      (node (ref "R33") (pin "1") (pinfunction "1_1") (pintype "passive"))
      (node (ref "U$5") (pin "AMP_BIAS_1") (pinfunction "AMP_BIAS_1_AMP_BIAS_1") (pintype "input"))
    )
    (net (code "55") (name "Net-(R36-Pad1)") (class "Default")
      (node (ref "R36") (pin "1") (pinfunction "1_1") (pintype "passive"))
      (node (ref "U$5") (pin "DIODE_BIAS_2") (pinfunction "DIODE_BIAS_2_DIODE_BIAS_2") (pintype "input"))
    )
    (net (code "56") (name "Net-(R37-Pad2)") (class "Default")
      (node (ref "R37") (pin "2") (pinfunction "2_2") (pintype "passive"))
      (node (ref "U$5") (pin "+IN_2") (pinfunction "+IN_2_+IN_2") (pintype "input"))
      (node (ref "VCA_TRIM") (pin "E") (pinfunction "E_E") (pintype "passive"))
    )
    (net (code "57") (name "Net-(R38-Pad2)") (class "Default")
      (node (ref "R38") (pin "2") (pinfunction "2_2") (pintype "passive"))
      (node (ref "U$5") (pin "OUT_2") (pinfunction "OUT_2_OUT_2") (pintype "output"))
      (node (ref "U$6") (pin "+IN_2") (pinfunction "+IN_2_+IN_2") (pintype "input"))
    )
    (net (code "58") (name "Net-(R39-Pad1)") (class "Default")
      (node (ref "R39") (pin "1") (pinfunction "1_1") (pintype "passive"))
      (node (ref "U$7") (pin "DIODE_BIAS_1") (pinfunction "DIODE_BIAS_1_DIODE_BIAS_1") (pintype "input"))
    )
    (net (code "59") (name "Net-(U$2A-B)") (class "Default")
      (node (ref "R5") (pin "1") (pinfunction "1_1") (pintype "passive"))
      (node (ref "U$2") (pin "Q1_B") (pinfunction "B_Q1_B") (pintype "bidirectional"))
    )
    (net (code "60") (name "Net-(U$2A-C)") (class "Default")
      (node (ref "C1") (pin "2") (pinfunction "2_2") (pintype "passive"))
      (node (ref "R7") (pin "1") (pinfunction "1_1") (pintype "passive"))
      (node (ref "U$1") (pin "OUT_1") (pinfunction "OUT_1_OUT_1") (pintype "output"))
      (node (ref "U$2") (pin "Q1_C") (pinfunction "C_Q1_C") (pintype "bidirectional"))
    )
    (net (code "61") (name "Net-(U$2B-B)") (class "Default")
      (node (ref "D3") (pin "C") (pinfunction "C_C") (pintype "passive"))
      (node (ref "R24") (pin "1") (pinfunction "1_1") (pintype "passive"))
      (node (ref "U$2") (pin "Q2_B") (pinfunction "B_Q2_B") (pintype "bidirectional"))
      (node (ref "U$2") (pin "Q3_B") (pinfunction "B_Q3_B") (pintype "bidirectional"))
    )
    (net (code "62") (name "Net-(U$2B-E)") (class "Default")
      (node (ref "U$2") (pin "Q2_E") (pinfunction "E_Q2_E") (pintype "bidirectional"))
      (node (ref "U$2") (pin "Q3_E") (pinfunction "E_Q3_E") (pintype "bidirectional"))
      (node (ref "U$5") (pin "OUT_1") (pinfunction "OUT_1_OUT_1") (pintype "output"))
    )
    (net (code "63") (name "Net-(U$2C-C)") (class "Default")
      (node (ref "U$2") (pin "Q3_C") (pinfunction "C_Q3_C") (pintype "bidirectional"))
      (node (ref "U$4") (pin "AMP_BIAS_2") (pinfunction "AMP_BIAS_2_AMP_BIAS_2") (pintype "input"))
    )
    (net (code "64") (name "Net-(U$5-Pad-IN_2)") (class "Default")
      (node (ref "U$5") (pin "-IN_2") (pinfunction "-IN_2_-IN_2") (pintype "input"))
      (node (ref "VCA_TRIM") (pin "A") (pinfunction "A_A") (pintype "passive"))
    )
    (net (code "65") (name "Net-(U$5-PadAMP_BIAS_2)") (class "Default")
      (node (ref "U$5") (pin "AMP_BIAS_2") (pinfunction "AMP_BIAS_2_AMP_BIAS_2") (pintype "input"))
      (node (ref "U$7") (pin "OUT_1") (pinfunction "OUT_1_OUT_1") (pintype "output"))
    )
    (net (code "66") (name "Net-(U$7-Pad-IN_1)") (class "Default")
      (node (ref "U$7") (pin "-IN_1") (pinfunction "-IN_1_-IN_1") (pintype "input"))
      (node (ref "VCA_TRIM1") (pin "A") (pinfunction "A_A") (pintype "passive"))
    )
    (net (code "67") (name "unconnected-(IC1-DB-Pad9)") (class "Default")
      (node (ref "IC1") (pin "9") (pinfunction "DB_9") (pintype "passive"))
    )
    (net (code "68") (name "unconnected-(IC1-EN-Pad2)") (class "Default")
      (node (ref "IC1") (pin "2") (pinfunction "EN_2") (pintype "input"))
    )
    (net (code "69") (name "unconnected-(IC1-S1B-Pad13)") (class "Default")
      (node (ref "IC1") (pin "13") (pinfunction "S1B_13") (pintype "passive"))
    )
    (net (code "70") (name "unconnected-(IC1-S2B-Pad12)") (class "Default")
      (node (ref "IC1") (pin "12") (pinfunction "S2B_12") (pintype "passive"))
    )
    (net (code "71") (name "unconnected-(IC1-S3B-Pad11)") (class "Default")
      (node (ref "IC1") (pin "11") (pinfunction "S3B_11") (pintype "passive"))
    )
    (net (code "72") (name "unconnected-(IC1-S4B-Pad10)") (class "Default")
      (node (ref "IC1") (pin "10") (pinfunction "S4B_10") (pintype "passive"))
    )
    (net (code "73") (name "unconnected-(IC2-DB-Pad9)") (class "Default")
      (node (ref "IC2") (pin "9") (pinfunction "DB_9") (pintype "passive"))
    )
    (net (code "74") (name "unconnected-(IC2-EN-Pad2)") (class "Default")
      (node (ref "IC2") (pin "2") (pinfunction "EN_2") (pintype "input"))
    )
    (net (code "75") (name "unconnected-(IC2-S1B-Pad13)") (class "Default")
      (node (ref "IC2") (pin "13") (pinfunction "S1B_13") (pintype "passive"))
    )
    (net (code "76") (name "unconnected-(IC2-S2B-Pad12)") (class "Default")
      (node (ref "IC2") (pin "12") (pinfunction "S2B_12") (pintype "passive"))
    )
    (net (code "77") (name "unconnected-(IC2-S3B-Pad11)") (class "Default")
      (node (ref "IC2") (pin "11") (pinfunction "S3B_11") (pintype "passive"))
    )
    (net (code "78") (name "unconnected-(IC2-S4A-Pad7)") (class "Default")
      (node (ref "IC2") (pin "7") (pinfunction "S4A_7") (pintype "passive"))
    )
    (net (code "79") (name "unconnected-(IC2-S4B-Pad10)") (class "Default")
      (node (ref "IC2") (pin "10") (pinfunction "S4B_10") (pintype "passive"))
    )
    (net (code "80") (name "unconnected-(IC3-DB-Pad9)") (class "Default")
      (node (ref "IC3") (pin "9") (pinfunction "DB_9") (pintype "passive"))
    )
    (net (code "81") (name "unconnected-(IC3-EN-Pad2)") (class "Default")
      (node (ref "IC3") (pin "2") (pinfunction "EN_2") (pintype "input"))
    )
    (net (code "82") (name "unconnected-(IC3-S1B-Pad13)") (class "Default")
      (node (ref "IC3") (pin "13") (pinfunction "S1B_13") (pintype "passive"))
    )
    (net (code "83") (name "unconnected-(IC3-S2B-Pad12)") (class "Default")
      (node (ref "IC3") (pin "12") (pinfunction "S2B_12") (pintype "passive"))
    )
    (net (code "84") (name "unconnected-(IC3-S3B-Pad11)") (class "Default")
      (node (ref "IC3") (pin "11") (pinfunction "S3B_11") (pintype "passive"))
    )
    (net (code "85") (name "unconnected-(IC3-S4A-Pad7)") (class "Default")
      (node (ref "IC3") (pin "7") (pinfunction "S4A_7") (pintype "passive"))
    )
    (net (code "86") (name "unconnected-(IC3-S4B-Pad10)") (class "Default")
      (node (ref "IC3") (pin "10") (pinfunction "S4B_10") (pintype "passive"))
    )
    (net (code "87") (name "unconnected-(R2-Pad1)") (class "Default")
      (node (ref "R2") (pin "1") (pinfunction "1_1") (pintype "passive"))
    )
    (net (code "88") (name "unconnected-(R3-Pad1)") (class "Default")
      (node (ref "R3") (pin "1") (pinfunction "1_1") (pintype "passive"))
    )
    (net (code "89") (name "unconnected-(R40-Pad1)") (class "Default")
      (node (ref "R40") (pin "1") (pinfunction "1_1") (pintype "passive"))
    )
    (net (code "90") (name "unconnected-(U$2B-C-PadQ2_C)") (class "Default")
      (node (ref "U$2") (pin "Q2_C") (pinfunction "C_Q2_C") (pintype "bidirectional"))
    )
    (net (code "91") (name "unconnected-(U$4-PadAMP_BIAS_1)") (class "Default")
      (node (ref "U$4") (pin "AMP_BIAS_1") (pinfunction "AMP_BIAS_1_AMP_BIAS_1") (pintype "input"))
    )
    (net (code "92") (name "unconnected-(U$7-PadAMP_BIAS_1)") (class "Default")
      (node (ref "U$7") (pin "AMP_BIAS_1") (pinfunction "AMP_BIAS_1_AMP_BIAS_1") (pintype "input"))
    )
  )
)
